# 3_Sterowanie_kluczem.net
KiCad netlist of a schematic drawn in Altium Designer
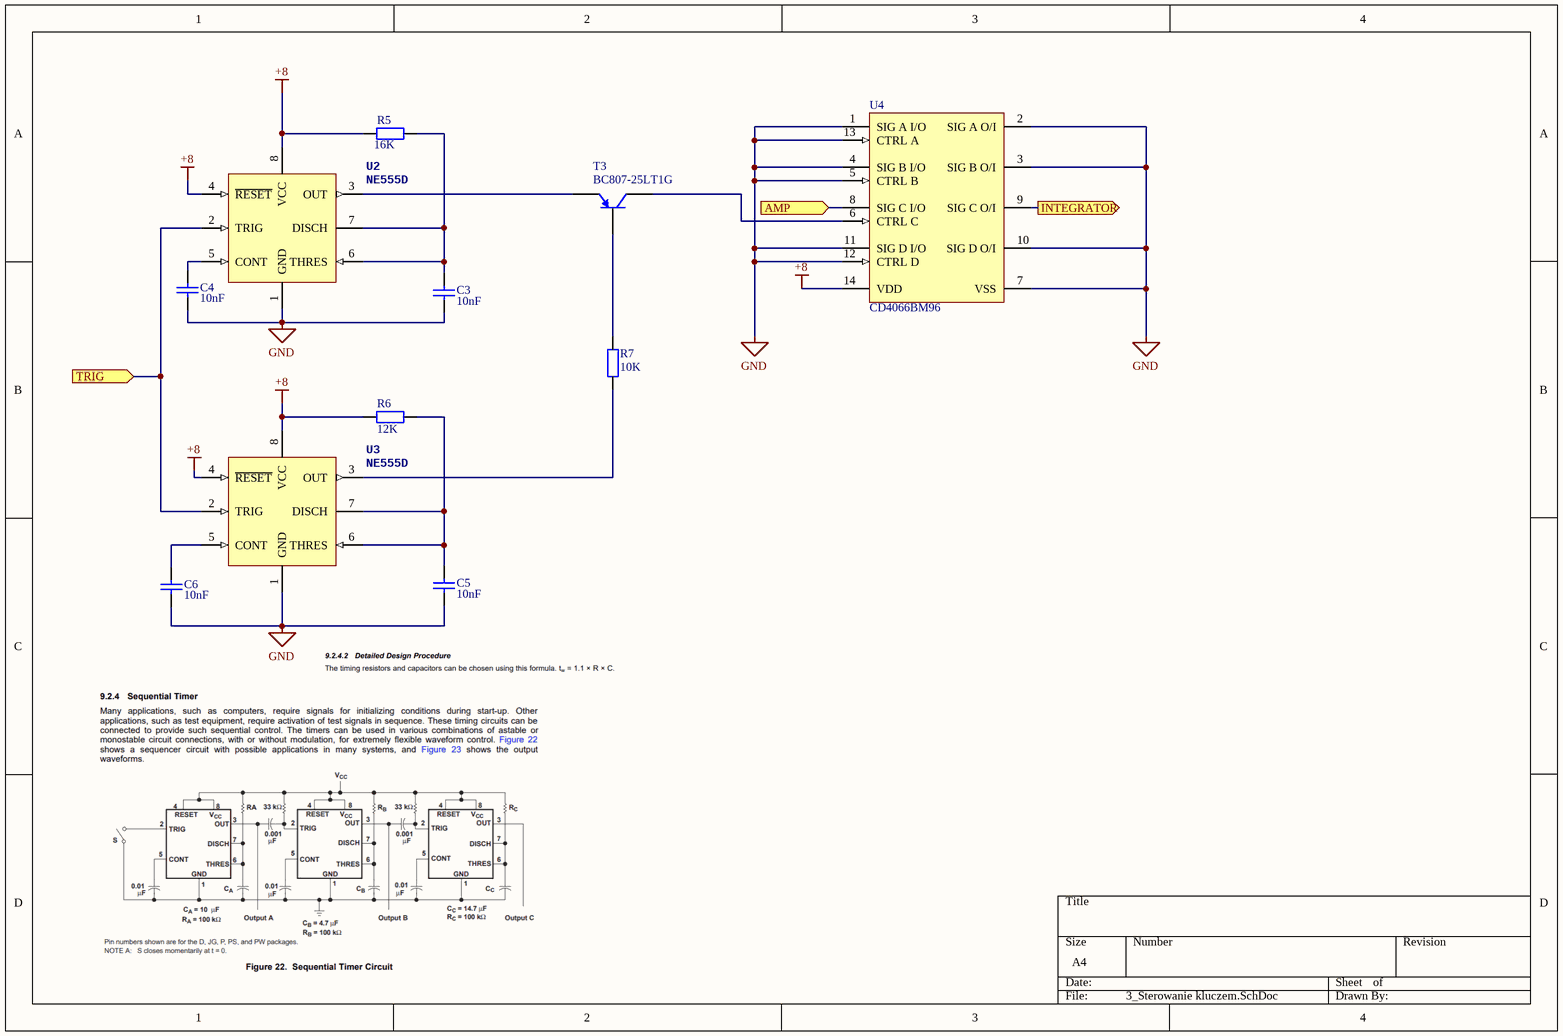
[diagram p0: 3_Sterowanie kluczem.SchDoc]

(export (version "E")
  (design (tool "Eeschema 10.0.6"))
  (components
    (comp (ref "C3")
      (value "VJ0603Y103KNAAO")
      (footprint "CAPC1608X92X38NL15T08")
      (fields (field (name "MANUFACTURER") "Vitramon") (field (name "CAPACITANCE") "10nF"))
      (libsource (lib "Altium Content Vault") (part "CAP"))
    )
    (comp (ref "C4")
      (value "VJ0603Y103KNAAO")
      (footprint "CAPC1608X92X38NL15T08")
      (fields (field (name "MANUFACTURER") "Vitramon") (field (name "CAPACITANCE") "10nF"))
      (libsource (lib "Altium Content Vault") (part "CAP"))
    )
    (comp (ref "C5")
      (value "VJ0603Y103KNAAO")
      (footprint "CAPC1608X92X38NL15T08")
      (fields (field (name "MANUFACTURER") "Vitramon") (field (name "CAPACITANCE") "10nF"))
      (libsource (lib "Altium Content Vault") (part "CAP"))
    )
    (comp (ref "C6")
      (value "VJ0603Y103KNAAO")
      (footprint "CAPC1608X92X38NL15T08")
      (fields (field (name "MANUFACTURER") "Vitramon") (field (name "CAPACITANCE") "10nF"))
      (libsource (lib "Altium Content Vault") (part "CAP"))
    )
    (comp (ref "R5")
      (value "16K")
      (footprint "R1206")
      (description "Resistor")
      (fields (field (name "Comment") "1206S4J0163T5E@TME") (field (name "PUBLISHER") "Altium Limited"))
      (libsource (lib "MT_Library") (part "Res2"))
    )
    (comp (ref "R6")
      (value "12K")
      (footprint "R1206")
      (description "Resistor")
      (fields (field (name "Comment") "1206S4J0123T5E@TME") (field (name "PUBLISHER") "Altium Limited"))
      (libsource (lib "Miscellaneous Devices") (part "Res2"))
    )
    (comp (ref "R7")
      (value "10K")
      (footprint "R1206")
      (description "Resistor")
      (libsource (lib "MT_Library") (part "Res"))
    )
    (comp (ref "T3")
      (value "BC807-25LT1G")
      (footprint "ONSC-SOT-23-3-318-08_V")
      (description "General Purpose Transistor, PNP Silicon, 3-Pin SOT-23, Pb-Free, Tape and Reel")
      (fields (field (name "MANUFACTURER") "On Semiconductor"))
      (libsource (lib "Altium Content Vault") (part "ONSC-PNP-B1E2C3-3"))
    )
    (comp (ref "U2")
      (value "NE555D")
      (footprint "D0008A_N")
      (description "Precision Timer, 4.5 to 16 V, 0 to 70 degC, 8-Pin SOIC (D), Green (RoHS & no Sb/Br), Tube")
      (fields (field (name "PARTNUMBER") "NE555") (field (name "MANUFACTURER") "Texas Instruments"))
      (libsource (lib "NE555D") (part "CMP-2000-06840-1"))
    )
    (comp (ref "U3")
      (value "NE555D")
      (footprint "D0008A_N")
      (description "Precision Timer, 4.5 to 16 V, 0 to 70 degC, 8-Pin SOIC (D), Green (RoHS & no Sb/Br), Tube")
      (fields (field (name "PARTNUMBER") "NE555") (field (name "MANUFACTURER") "Texas Instruments"))
      (libsource (lib "NE555D") (part "CMP-2000-06840-1"))
    )
    (comp (ref "U4")
      (value "CD4066BM96")
      (footprint "D0014A_M")
      (description "CMOS Quad Bilateral Switch, D0014A, LARGE T&R")
      (fields
        (field (name "MANUFACTURER") "Texas Instruments")
        (field (name "GENERIC PART NUMBER") "CD4066B")
      )
      (libsource (lib "Altium Content Vault") (part "TI-CD4066B-14"))
    )
  )
  (nets
    (net (code "1") (name "+8") (class "Default")
      (node (ref "R5") (pin "1") (pinfunction "1_1") (pintype "passive"))
      (node (ref "R6") (pin "1") (pinfunction "1_1") (pintype "passive"))
      (node (ref "U2") (pin "4") (pinfunction "~{RESET}_4") (pintype "input"))
      (node (ref "U2") (pin "8") (pinfunction "VCC_8") (pintype "power_in"))
      (node (ref "U3") (pin "4") (pinfunction "~{RESET}_4") (pintype "input"))
      (node (ref "U3") (pin "8") (pinfunction "VCC_8") (pintype "power_in"))
      (node (ref "U4") (pin "14") (pinfunction "VDD_14") (pintype "power_in"))
    )
    (net (code "2") (name "/AMP") (class "Default")
      (node (ref "U4") (pin "8") (pinfunction "SIG_C_I/O_8") (pintype "passive"))
    )
    (net (code "3") (name "/INTEGRATOR") (class "Default")
      (node (ref "U4") (pin "9") (pinfunction "SIG_C_O/I_9") (pintype "passive"))
    )
    (net (code "4") (name "/TRIG") (class "Default")
      (node (ref "U2") (pin "2") (pinfunction "TRIG_2") (pintype "input"))
      (node (ref "U3") (pin "2") (pinfunction "TRIG_2") (pintype "input"))
    )
    (net (code "5") (name "GND") (class "Default")
      (node (ref "C3") (pin "1") (pinfunction "1_1") (pintype "passive"))
      (node (ref "C4") (pin "1") (pinfunction "1_1") (pintype "passive"))
      (node (ref "C5") (pin "1") (pinfunction "1_1") (pintype "passive"))
      (node (ref "C6") (pin "1") (pinfunction "1_1") (pintype "passive"))
      (node (ref "U2") (pin "1") (pinfunction "GND_1") (pintype "power_in"))
      (node (ref "U3") (pin "1") (pinfunction "GND_1") (pintype "power_in"))
      (node (ref "U4") (pin "1") (pinfunction "SIG_A_I/O_1") (pintype "passive"))
      (node (ref "U4") (pin "10") (pinfunction "SIG_D_O/I_10") (pintype "passive"))
      (node (ref "U4") (pin "11") (pinfunction "SIG_D_I/O_11") (pintype "passive"))
      (node (ref "U4") (pin "12") (pinfunction "CTRL_D_12") (pintype "input"))
      (node (ref "U4") (pin "13") (pinfunction "CTRL_A_13") (pintype "input"))
      (node (ref "U4") (pin "2") (pinfunction "SIG_A_O/I_2") (pintype "passive"))
      (node (ref "U4") (pin "3") (pinfunction "SIG_B_O/I_3") (pintype "passive"))
      (node (ref "U4") (pin "4") (pinfunction "SIG_B_I/O_4") (pintype "passive"))
      (node (ref "U4") (pin "5") (pinfunction "CTRL_B_5") (pintype "input"))
      (node (ref "U4") (pin "7") (pinfunction "VSS_7") (pintype "power_in"))
    )
    (net (code "6") (name "Net-(T3-B)") (class "Default")
      (node (ref "R7") (pin "2") (pinfunction "2_2") (pintype "passive"))
      (node (ref "T3") (pin "1") (pinfunction "B_1") (pintype "passive"))
    )
    (net (code "7") (name "Net-(T3-C)") (class "Default")
      (node (ref "T3") (pin "3") (pinfunction "C_3") (pintype "passive"))
      (node (ref "U4") (pin "6") (pinfunction "CTRL_C_6") (pintype "input"))
    )
    (net (code "8") (name "Net-(T3-E)") (class "Default")
      (node (ref "T3") (pin "2") (pinfunction "E_2") (pintype "passive"))
      (node (ref "U2") (pin "3") (pinfunction "OUT_3") (pintype "output"))
    )
    (net (code "9") (name "Net-(U2-CONT)") (class "Default")
      (node (ref "C4") (pin "2") (pinfunction "2_2") (pintype "passive"))
      (node (ref "U2") (pin "5") (pinfunction "CONT_5") (pintype "input"))
    )
    (net (code "10") (name "Net-(U2-DISCH)") (class "Default")
      (node (ref "C3") (pin "2") (pinfunction "2_2") (pintype "passive"))
      (node (ref "R5") (pin "2") (pinfunction "2_2") (pintype "passive"))
      (node (ref "U2") (pin "6") (pinfunction "THRES_6") (pintype "input"))
      (node (ref "U2") (pin "7") (pinfunction "DISCH_7") (pintype "open_collector"))
    )
    (net (code "11") (name "Net-(U3-CONT)") (class "Default")
      (node (ref "C6") (pin "2") (pinfunction "2_2") (pintype "passive"))
      (node (ref "U3") (pin "5") (pinfunction "CONT_5") (pintype "input"))
    )
    (net (code "12") (name "Net-(U3-DISCH)") (class "Default")
      (node (ref "C5") (pin "2") (pinfunction "2_2") (pintype "passive"))
      (node (ref "R6") (pin "2") (pinfunction "2_2") (pintype "passive"))
      (node (ref "U3") (pin "6") (pinfunction "THRES_6") (pintype "input"))
      (node (ref "U3") (pin "7") (pinfunction "DISCH_7") (pintype "open_collector"))
    )
    (net (code "13") (name "Net-(U3-OUT)") (class "Default")
      (node (ref "R7") (pin "1") (pinfunction "1_1") (pintype "passive"))
      (node (ref "U3") (pin "3") (pinfunction "OUT_3") (pintype "output"))
    )
  )
)
